# RD.net
KiCad netlist of a schematic drawn in Altium Designer
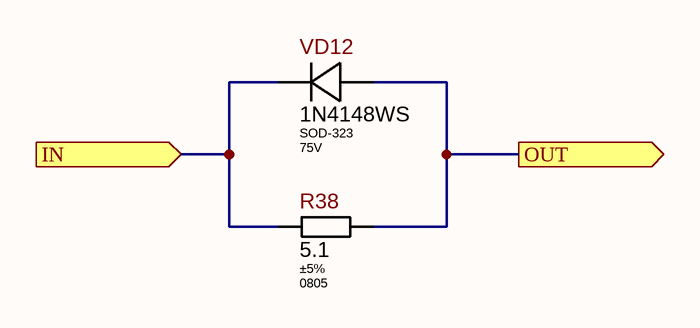
[diagram p0: RD.SchDoc]

(export (version "E")
  (design (tool "Eeschema 10.0.6"))
  (components
    (comp (ref "R38")
      (value "5.1")
      (footprint "R_ANY_CHIP_0805_MED")
      (description "5.1 Ohms ±5%, 1/8W 0805 Thick Film Resistor")
      (fields
        (field (name "TOLERANCE") "±5%")
        (field (name "PACKAGE") "0805")
        (field (name "PART NUMBER") "RC0805JR-075R1L")
        (field (name "MANUFACTURER") "Yageo")
      )
      (libsource (lib "resistors") (part "RC0805JR-075R1L"))
    )
    (comp (ref "VD12")
      (value "1N4148WS")
      (footprint "SOD-323_MED")
      (description "Diode Standard 75V 150mA, SOD-323F")
      (fields
        (field (name "MANUFACTURER") "Diodec Semiconductor")
        (field (name "PART NUMBER") "1N4148WS")
        (field (name "PACKAGE") "SOD-323")
        (field (name "VOLTAGE") "75V")
      )
      (libsource (lib "diodes") (part "1N4148WS"))
    )
  )
  (nets
    (net (code "1") (name "/IN") (class "Default")
      (node (ref "R38") (pin "1") (pintype "passive"))
      (node (ref "VD12") (pin "CA") (pintype "passive"))
    )
    (net (code "2") (name "/OUT") (class "Default")
      (node (ref "R38") (pin "2") (pintype "passive"))
      (node (ref "VD12") (pin "AN") (pintype "passive"))
    )
  )
)
